# DAC_STM32_Board_v4_-_AD5391.net
KiCad netlist of a schematic drawn in EAGLE
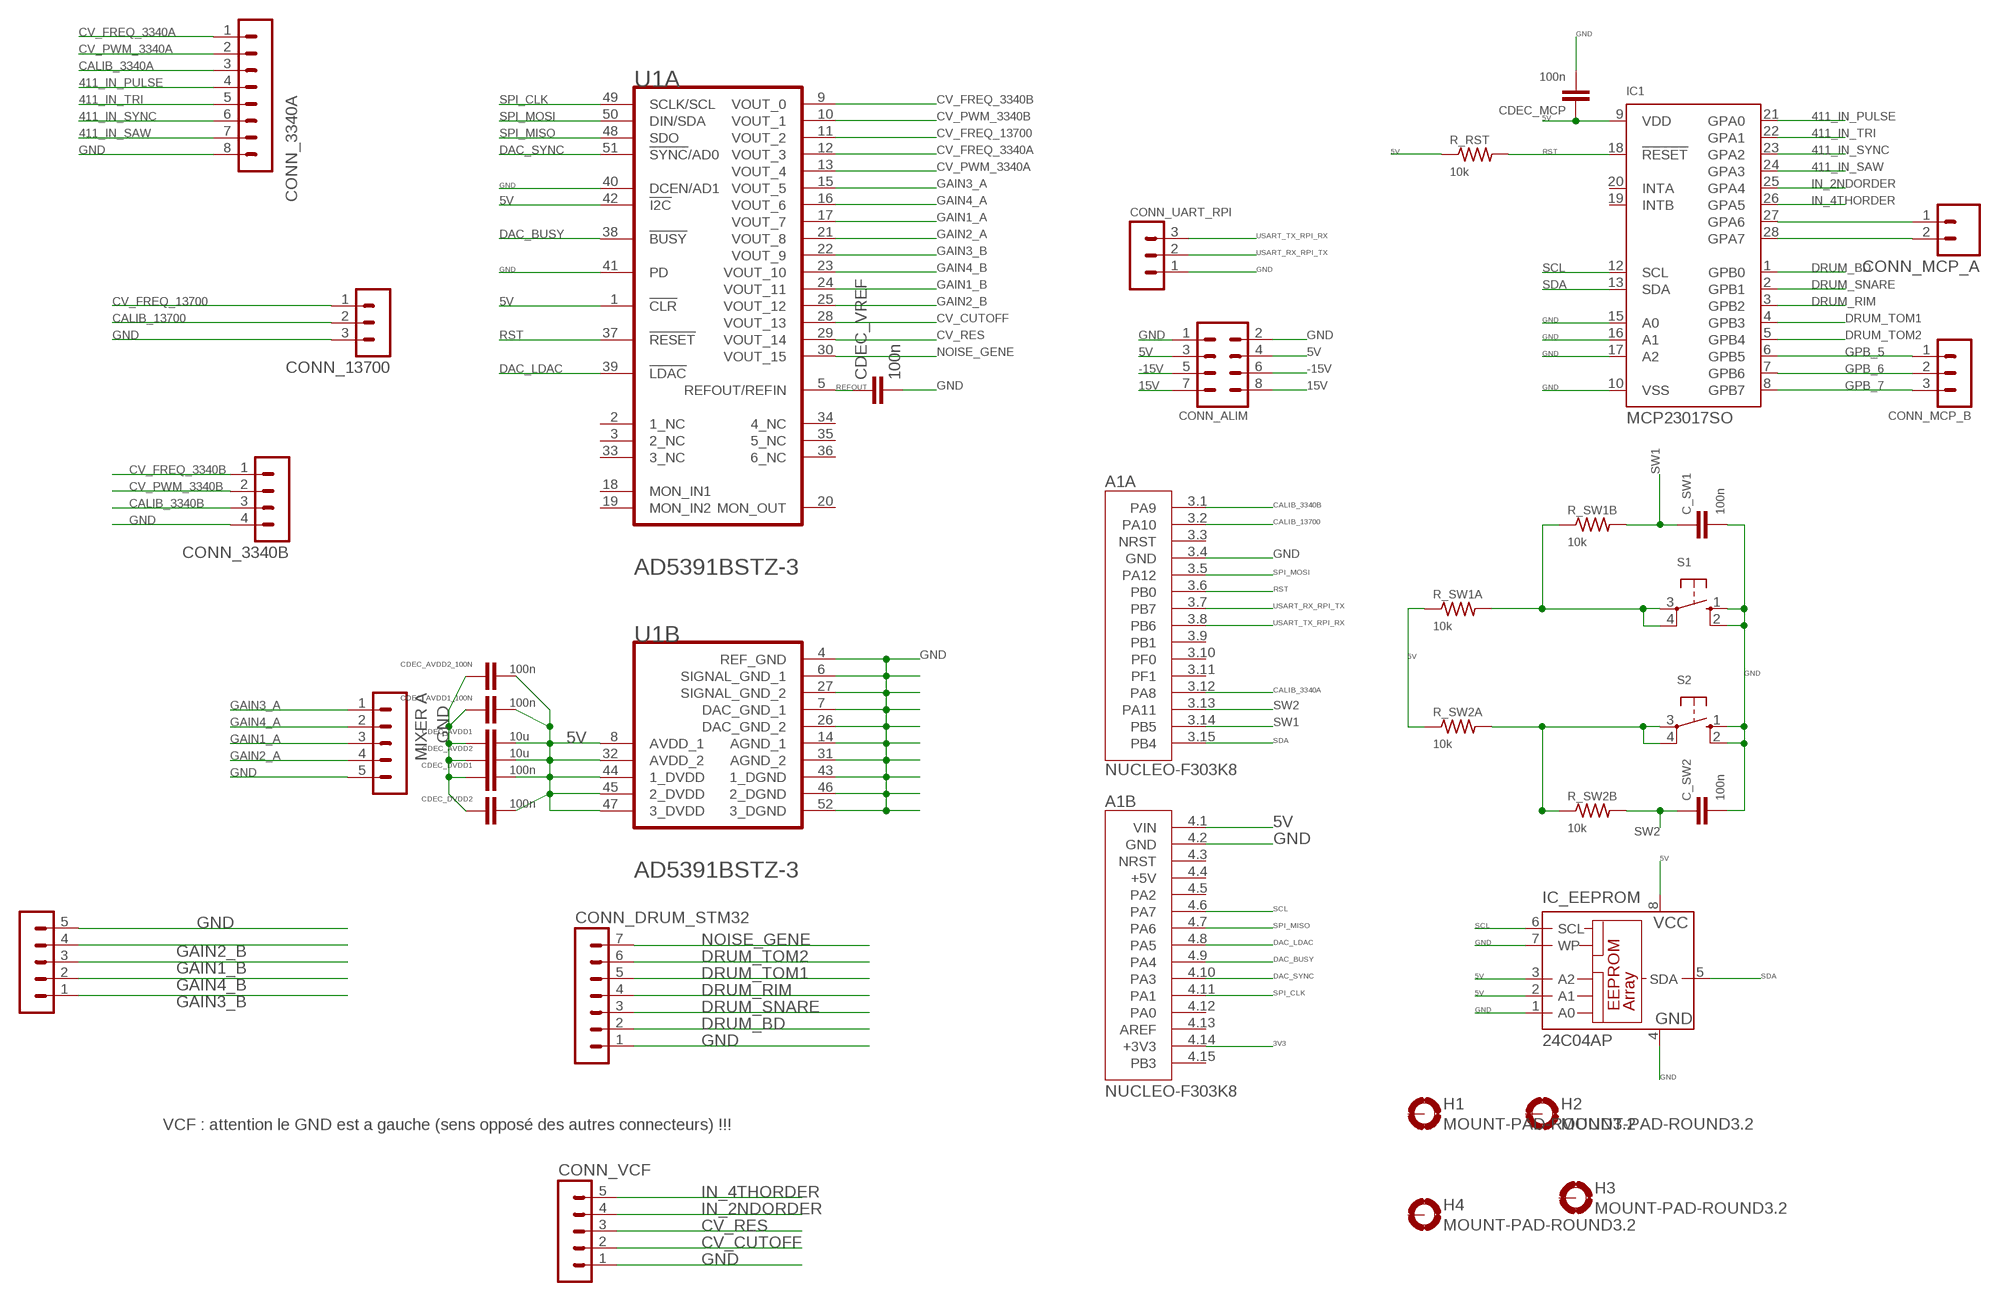
[diagram p0: schematic, sheet 1]

(export (version "E")
  (design (tool "Eeschema 10.0.6"))
  (components
    (comp (ref "A1")
      (value "NUCLEO-F303K8")
      (footprint "eagle-import:MODULE_NUCLEO-F303K8")
      (fields (field (name "DIGI-KEY_PART_NUMBER") "497-15981-ND") (field (name "MF") "STMicroelectronics"))
      (libsource (lib "eagle-import") (part "NUCLEO-F303K8"))
    )
    (comp (ref "CDEC_AVDD1")
      (value "10u")
      (footprint "eagle-import:C050-030X075")
      (libsource (lib "eagle-import") (part "C-EU050-030X075"))
    )
    (comp (ref "CDEC_AVDD1_100N")
      (value "100n")
      (footprint "eagle-import:C050-030X075")
      (libsource (lib "eagle-import") (part "C-EU050-030X075"))
    )
    (comp (ref "CDEC_AVDD2")
      (value "10u")
      (footprint "eagle-import:C050-030X075")
      (libsource (lib "eagle-import") (part "C-EU050-030X075"))
    )
    (comp (ref "CDEC_AVDD2_100N")
      (value "100n")
      (footprint "eagle-import:C050-030X075")
      (libsource (lib "eagle-import") (part "C-EU050-030X075"))
    )
    (comp (ref "CDEC_DVDD1")
      (value "100n")
      (footprint "eagle-import:C075-032X103")
      (libsource (lib "eagle-import") (part "C-EU075-032X103"))
    )
    (comp (ref "CDEC_DVDD2")
      (value "100n")
      (footprint "eagle-import:C050-030X075")
      (libsource (lib "eagle-import") (part "C-EU050-030X075"))
    )
    (comp (ref "CDEC_MCP")
      (value "100n")
      (footprint "eagle-import:C075-032X103")
      (libsource (lib "eagle-import") (part "C-EU075-032X103"))
    )
    (comp (ref "CDEC_VREF")
      (value "100n")
      (footprint "eagle-import:C050-030X075")
      (libsource (lib "eagle-import") (part "C-EU050-030X075"))
    )
    (comp (ref "CONN_3340A")
      (value "MA08-1")
      (footprint "eagle-import:MA08-1")
      (libsource (lib "eagle-import") (part "MA08-1"))
    )
    (comp (ref "CONN_3340B")
      (value "MA04-1")
      (footprint "eagle-import:MA04-1")
      (libsource (lib "eagle-import") (part "MA04-1"))
    )
    (comp (ref "CONN_13700")
      (value "MA03-1")
      (footprint "eagle-import:MA03-1")
      (libsource (lib "eagle-import") (part "MA03-1"))
    )
    (comp (ref "CONN_ALIM")
      (value "MA04-2")
      (footprint "eagle-import:MA04-2")
      (libsource (lib "eagle-import") (part "MA04-2"))
    )
    (comp (ref "CONN_DRUM_STM32")
      (value "MA07-1")
      (footprint "eagle-import:MA07-1")
      (libsource (lib "eagle-import") (part "MA07-1"))
    )
    (comp (ref "CONN_MCP_A")
      (value "M02")
      (footprint "eagle-import:02P")
      (libsource (lib "eagle-import") (part "M02"))
    )
    (comp (ref "CONN_MCP_B")
      (value "MA03-1")
      (footprint "eagle-import:MA03-1")
      (libsource (lib "eagle-import") (part "MA03-1"))
    )
    (comp (ref "CONN_MIX_A")
      (value "MA05-1")
      (footprint "eagle-import:MA05-1")
      (libsource (lib "eagle-import") (part "MA05-1"))
    )
    (comp (ref "CONN_MIX_B")
      (value "MA05-1")
      (footprint "eagle-import:MA05-1")
      (libsource (lib "eagle-import") (part "MA05-1"))
    )
    (comp (ref "CONN_UART_RPI")
      (value "MA03-1")
      (footprint "eagle-import:MA03-1")
      (libsource (lib "eagle-import") (part "MA03-1"))
    )
    (comp (ref "CONN_VCF")
      (value "MA05-1")
      (footprint "eagle-import:MA05-1")
      (libsource (lib "eagle-import") (part "MA05-1"))
    )
    (comp (ref "C_SW1")
      (value "100n")
      (footprint "eagle-import:C050-030X075")
      (libsource (lib "eagle-import") (part "C-EU050-030X075"))
    )
    (comp (ref "C_SW2")
      (value "100n")
      (footprint "eagle-import:C050-030X075")
      (libsource (lib "eagle-import") (part "C-EU050-030X075"))
    )
    (comp (ref "H1")
      (value "MOUNT-PAD-ROUND3.2")
      (footprint "eagle-import:3,2-PAD")
      (libsource (lib "eagle-import") (part "MOUNT-PAD-ROUND3.2"))
    )
    (comp (ref "H2")
      (value "MOUNT-PAD-ROUND3.2")
      (footprint "eagle-import:3,2-PAD")
      (libsource (lib "eagle-import") (part "MOUNT-PAD-ROUND3.2"))
    )
    (comp (ref "H3")
      (value "MOUNT-PAD-ROUND3.2")
      (footprint "eagle-import:3,2-PAD")
      (libsource (lib "eagle-import") (part "MOUNT-PAD-ROUND3.2"))
    )
    (comp (ref "H4")
      (value "MOUNT-PAD-ROUND3.2")
      (footprint "eagle-import:3,2-PAD")
      (libsource (lib "eagle-import") (part "MOUNT-PAD-ROUND3.2"))
    )
    (comp (ref "IC1")
      (value "MCP23017SO")
      (footprint "eagle-import:SO28W")
      (fields (field (name "MF") "MICROCHIP") (field (name "MPN") "MCP23017-E/SO"))
      (libsource (lib "eagle-import") (part "MCP23017SO"))
    )
    (comp (ref "IC_EEPROM")
      (value "24C04AP")
      (footprint "eagle-import:DIL8")
      (fields (field (name "MPN") "AT24C04B-PU"))
      (libsource (lib "eagle-import") (part "24CP04A"))
    )
    (comp (ref "R_RST")
      (value "10k")
      (footprint "eagle-import:0207_10")
      (libsource (lib "eagle-import") (part "R-US_0207/10"))
    )
    (comp (ref "R_SW1A")
      (value "10k")
      (footprint "eagle-import:0207_10")
      (libsource (lib "eagle-import") (part "R-US_0207/10"))
    )
    (comp (ref "R_SW1B")
      (value "10k")
      (footprint "eagle-import:0207_10")
      (libsource (lib "eagle-import") (part "R-US_0207/10"))
    )
    (comp (ref "R_SW2A")
      (value "10k")
      (footprint "eagle-import:0207_10")
      (libsource (lib "eagle-import") (part "R-US_0207/10"))
    )
    (comp (ref "R_SW2B")
      (value "10k")
      (footprint "eagle-import:0207_10")
      (libsource (lib "eagle-import") (part "R-US_0207/10"))
    )
    (comp (ref "S1")
      (value "10-XX")
      (footprint "eagle-import:B3F-10XX")
      (fields (field (name "MPN") "B3F-1000"))
      (libsource (lib "eagle-import") (part "10-XX"))
    )
    (comp (ref "S2")
      (value "10-XX")
      (footprint "eagle-import:B3F-10XX")
      (fields (field (name "MPN") "B3F-1000"))
      (libsource (lib "eagle-import") (part "10-XX"))
    )
    (comp (ref "U1")
      (value "ANALOG_DEVICES_AD5391BSTZ-3ANALOG_DEVICES_AD5391BSTZ-3_0_0")
      (footprint "eagle-import:ANALOG_DEVICES_AD5391BSTZ-3_0")
      (fields (field (name "MF") "Analog Devices") (field (name "MPN") "AD5391BSTZ-3"))
      (libsource (lib "eagle-import") (part "ANALOG_DEVICES_AD5391BSTZ-3ANALOG_DEVICES_AD5391BSTZ-3_0_0"))
    )
  )
  (nets
    (net (code "1") (name "/-15V") (class "Default")
      (node (ref "CONN_ALIM") (pin "5") (pinfunction "5_5") (pintype "passive"))
      (node (ref "CONN_ALIM") (pin "6") (pinfunction "6_6") (pintype "passive"))
    )
    (net (code "2") (name "/3V3") (class "Default")
      (node (ref "A1") (pin "4.14") (pinfunction "+3V3_4.14") (pintype "bidirectional"))
    )
    (net (code "3") (name "/5V") (class "Default")
      (node (ref "A1") (pin "4.1") (pinfunction "VIN_4.1") (pintype "bidirectional"))
      (node (ref "CDEC_AVDD1") (pin "2") (pinfunction "2_2") (pintype "passive"))
      (node (ref "CDEC_AVDD1_100N") (pin "2") (pinfunction "2_2") (pintype "passive"))
      (node (ref "CDEC_AVDD2") (pin "2") (pinfunction "2_2") (pintype "passive"))
      (node (ref "CDEC_AVDD2_100N") (pin "2") (pinfunction "2_2") (pintype "passive"))
      (node (ref "CDEC_DVDD1") (pin "2") (pinfunction "2_2") (pintype "passive"))
      (node (ref "CDEC_DVDD2") (pin "2") (pinfunction "2_2") (pintype "passive"))
      (node (ref "CDEC_MCP") (pin "1") (pinfunction "1_1") (pintype "passive"))
      (node (ref "CONN_ALIM") (pin "3") (pinfunction "3_3") (pintype "passive"))
      (node (ref "CONN_ALIM") (pin "4") (pinfunction "4_4") (pintype "passive"))
      (node (ref "IC1") (pin "9") (pinfunction "VDD_9") (pintype "power_in"))
      (node (ref "IC_EEPROM") (pin "2") (pinfunction "A1_2") (pintype "input"))
      (node (ref "IC_EEPROM") (pin "3") (pinfunction "A2_3") (pintype "input"))
      (node (ref "IC_EEPROM") (pin "8") (pinfunction "VCC_8") (pintype "power_in"))
      (node (ref "R_RST") (pin "1") (pinfunction "1_1") (pintype "passive"))
      (node (ref "R_SW1A") (pin "1") (pinfunction "1_1") (pintype "passive"))
      (node (ref "R_SW2A") (pin "1") (pinfunction "1_1") (pintype "passive"))
      (node (ref "U1") (pin "1") (pinfunction "~{CLR}_1") (pintype "input"))
      (node (ref "U1") (pin "32") (pinfunction "AVDD_2_32") (pintype "power_in"))
      (node (ref "U1") (pin "42") (pinfunction "~{I2C}_42") (pintype "input"))
      (node (ref "U1") (pin "44") (pinfunction "1_DVDD_44") (pintype "power_in"))
      (node (ref "U1") (pin "45") (pinfunction "2_DVDD_45") (pintype "power_in"))
      (node (ref "U1") (pin "47") (pinfunction "3_DVDD_47") (pintype "power_in"))
      (node (ref "U1") (pin "8") (pinfunction "AVDD_1_8") (pintype "power_in"))
    )
    (net (code "4") (name "/15V") (class "Default")
      (node (ref "CONN_ALIM") (pin "7") (pinfunction "7_7") (pintype "passive"))
      (node (ref "CONN_ALIM") (pin "8") (pinfunction "8_8") (pintype "passive"))
    )
    (net (code "5") (name "/411_IN_PULSE") (class "Default")
      (node (ref "CONN_3340A") (pin "4") (pinfunction "4_4") (pintype "passive"))
      (node (ref "IC1") (pin "21") (pinfunction "GPA0_21") (pintype "bidirectional"))
    )
    (net (code "6") (name "/411_IN_SAW") (class "Default")
      (node (ref "CONN_3340A") (pin "7") (pinfunction "7_7") (pintype "passive"))
      (node (ref "IC1") (pin "24") (pinfunction "GPA3_24") (pintype "bidirectional"))
    )
    (net (code "7") (name "/411_IN_SYNC") (class "Default")
      (node (ref "CONN_3340A") (pin "6") (pinfunction "6_6") (pintype "passive"))
      (node (ref "IC1") (pin "23") (pinfunction "GPA2_23") (pintype "bidirectional"))
    )
    (net (code "8") (name "/411_IN_TRI") (class "Default")
      (node (ref "CONN_3340A") (pin "5") (pinfunction "5_5") (pintype "passive"))
      (node (ref "IC1") (pin "22") (pinfunction "GPA1_22") (pintype "bidirectional"))
    )
    (net (code "9") (name "/CALIB_3340A") (class "Default")
      (node (ref "A1") (pin "3.12") (pinfunction "PA8_3.12") (pintype "bidirectional"))
      (node (ref "CONN_3340A") (pin "3") (pinfunction "3_3") (pintype "passive"))
    )
    (net (code "10") (name "/CALIB_3340B") (class "Default")
      (node (ref "A1") (pin "3.1") (pinfunction "PA9_3.1") (pintype "bidirectional"))
      (node (ref "CONN_3340B") (pin "3") (pinfunction "3_3") (pintype "passive"))
    )
    (net (code "11") (name "/CALIB_13700") (class "Default")
      (node (ref "A1") (pin "3.2") (pinfunction "PA10_3.2") (pintype "bidirectional"))
      (node (ref "CONN_13700") (pin "2") (pinfunction "2_2") (pintype "passive"))
    )
    (net (code "12") (name "/CV_CUTOFF") (class "Default")
      (node (ref "CONN_VCF") (pin "2") (pinfunction "2_2") (pintype "passive"))
      (node (ref "U1") (pin "28") (pinfunction "VOUT_13_28") (pintype "tri_state"))
    )
    (net (code "13") (name "/CV_FREQ_3340A") (class "Default")
      (node (ref "CONN_3340A") (pin "1") (pinfunction "1_1") (pintype "passive"))
      (node (ref "U1") (pin "12") (pinfunction "VOUT_3_12") (pintype "tri_state"))
    )
    (net (code "14") (name "/CV_FREQ_3340B") (class "Default")
      (node (ref "CONN_3340B") (pin "1") (pinfunction "1_1") (pintype "passive"))
      (node (ref "U1") (pin "9") (pinfunction "VOUT_0_9") (pintype "tri_state"))
    )
    (net (code "15") (name "/CV_FREQ_13700") (class "Default")
      (node (ref "CONN_13700") (pin "1") (pinfunction "1_1") (pintype "passive"))
      (node (ref "U1") (pin "11") (pinfunction "VOUT_2_11") (pintype "tri_state"))
    )
    (net (code "16") (name "/CV_PWM_3340A") (class "Default")
      (node (ref "CONN_3340A") (pin "2") (pinfunction "2_2") (pintype "passive"))
      (node (ref "U1") (pin "13") (pinfunction "VOUT_4_13") (pintype "tri_state"))
    )
    (net (code "17") (name "/CV_PWM_3340B") (class "Default")
      (node (ref "CONN_3340B") (pin "2") (pinfunction "2_2") (pintype "passive"))
      (node (ref "U1") (pin "10") (pinfunction "VOUT_1_10") (pintype "tri_state"))
    )
    (net (code "18") (name "/CV_RES") (class "Default")
      (node (ref "CONN_VCF") (pin "3") (pinfunction "3_3") (pintype "passive"))
      (node (ref "U1") (pin "29") (pinfunction "VOUT_14_29") (pintype "tri_state"))
    )
    (net (code "19") (name "/DAC_BUSY") (class "Default")
      (node (ref "A1") (pin "4.9") (pinfunction "PA4_4.9") (pintype "bidirectional"))
      (node (ref "U1") (pin "38") (pinfunction "~{BUSY}_38") (pintype "output"))
    )
    (net (code "20") (name "/DAC_LDAC") (class "Default")
      (node (ref "A1") (pin "4.8") (pinfunction "PA5_4.8") (pintype "bidirectional"))
      (node (ref "U1") (pin "39") (pinfunction "~{LDAC}_39") (pintype "input"))
    )
    (net (code "21") (name "/DAC_SYNC") (class "Default")
      (node (ref "A1") (pin "4.10") (pinfunction "PA3_4.10") (pintype "bidirectional"))
      (node (ref "U1") (pin "51") (pinfunction "~{SYNC}/AD0_51") (pintype "input"))
    )
    (net (code "22") (name "/DRUM_BD") (class "Default")
      (node (ref "CONN_DRUM_STM32") (pin "2") (pinfunction "2_2") (pintype "passive"))
      (node (ref "IC1") (pin "1") (pinfunction "GPB0_1") (pintype "bidirectional"))
    )
    (net (code "23") (name "/DRUM_RIM") (class "Default")
      (node (ref "CONN_DRUM_STM32") (pin "4") (pinfunction "4_4") (pintype "passive"))
      (node (ref "IC1") (pin "3") (pinfunction "GPB2_3") (pintype "bidirectional"))
    )
    (net (code "24") (name "/DRUM_SNARE") (class "Default")
      (node (ref "CONN_DRUM_STM32") (pin "3") (pinfunction "3_3") (pintype "passive"))
      (node (ref "IC1") (pin "2") (pinfunction "GPB1_2") (pintype "bidirectional"))
    )
    (net (code "25") (name "/DRUM_TOM1") (class "Default")
      (node (ref "CONN_DRUM_STM32") (pin "5") (pinfunction "5_5") (pintype "passive"))
      (node (ref "IC1") (pin "4") (pinfunction "GPB3_4") (pintype "bidirectional"))
    )
    (net (code "26") (name "/DRUM_TOM2") (class "Default")
      (node (ref "CONN_DRUM_STM32") (pin "6") (pinfunction "6_6") (pintype "passive"))
      (node (ref "IC1") (pin "5") (pinfunction "GPB4_5") (pintype "bidirectional"))
    )
    (net (code "27") (name "/GAIN1_A") (class "Default")
      (node (ref "CONN_MIX_A") (pin "3") (pinfunction "3_3") (pintype "passive"))
      (node (ref "U1") (pin "17") (pinfunction "VOUT_7_17") (pintype "tri_state"))
    )
    (net (code "28") (name "/GAIN1_B") (class "Default")
      (node (ref "CONN_MIX_B") (pin "3") (pinfunction "3_3") (pintype "passive"))
      (node (ref "U1") (pin "24") (pinfunction "VOUT_11_24") (pintype "tri_state"))
    )
    (net (code "29") (name "/GAIN2_A") (class "Default")
      (node (ref "CONN_MIX_A") (pin "4") (pinfunction "4_4") (pintype "passive"))
      (node (ref "U1") (pin "21") (pinfunction "VOUT_8_21") (pintype "tri_state"))
    )
    (net (code "30") (name "/GAIN2_B") (class "Default")
      (node (ref "CONN_MIX_B") (pin "4") (pinfunction "4_4") (pintype "passive"))
      (node (ref "U1") (pin "25") (pinfunction "VOUT_12_25") (pintype "tri_state"))
    )
    (net (code "31") (name "/GAIN3_A") (class "Default")
      (node (ref "CONN_MIX_A") (pin "1") (pinfunction "1_1") (pintype "passive"))
      (node (ref "U1") (pin "15") (pinfunction "VOUT_5_15") (pintype "tri_state"))
    )
    (net (code "32") (name "/GAIN3_B") (class "Default")
      (node (ref "CONN_MIX_B") (pin "1") (pinfunction "1_1") (pintype "passive"))
      (node (ref "U1") (pin "22") (pinfunction "VOUT_9_22") (pintype "tri_state"))
    )
    (net (code "33") (name "/GAIN4_A") (class "Default")
      (node (ref "CONN_MIX_A") (pin "2") (pinfunction "2_2") (pintype "passive"))
      (node (ref "U1") (pin "16") (pinfunction "VOUT_6_16") (pintype "tri_state"))
    )
    (net (code "34") (name "/GAIN4_B") (class "Default")
      (node (ref "CONN_MIX_B") (pin "2") (pinfunction "2_2") (pintype "passive"))
      (node (ref "U1") (pin "23") (pinfunction "VOUT_10_23") (pintype "tri_state"))
    )
    (net (code "35") (name "/GND") (class "Default")
      (node (ref "A1") (pin "3.4") (pinfunction "GND_3.4") (pintype "bidirectional"))
      (node (ref "A1") (pin "4.2") (pinfunction "GND_4.2") (pintype "bidirectional"))
      (node (ref "CDEC_AVDD1") (pin "1") (pinfunction "1_1") (pintype "passive"))
      (node (ref "CDEC_AVDD1_100N") (pin "1") (pinfunction "1_1") (pintype "passive"))
      (node (ref "CDEC_AVDD2") (pin "1") (pinfunction "1_1") (pintype "passive"))
      (node (ref "CDEC_AVDD2_100N") (pin "1") (pinfunction "1_1") (pintype "passive"))
      (node (ref "CDEC_DVDD1") (pin "1") (pinfunction "1_1") (pintype "passive"))
      (node (ref "CDEC_DVDD2") (pin "1") (pinfunction "1_1") (pintype "passive"))
      (node (ref "CDEC_MCP") (pin "2") (pinfunction "2_2") (pintype "passive"))
      (node (ref "CDEC_VREF") (pin "2") (pinfunction "2_2") (pintype "passive"))
      (node (ref "CONN_13700") (pin "3") (pinfunction "3_3") (pintype "passive"))
      (node (ref "CONN_3340A") (pin "8") (pinfunction "8_8") (pintype "passive"))
      (node (ref "CONN_3340B") (pin "4") (pinfunction "4_4") (pintype "passive"))
      (node (ref "CONN_ALIM") (pin "1") (pinfunction "1_1") (pintype "passive"))
      (node (ref "CONN_ALIM") (pin "2") (pinfunction "2_2") (pintype "passive"))
      (node (ref "CONN_DRUM_STM32") (pin "1") (pinfunction "1_1") (pintype "passive"))
      (node (ref "CONN_MIX_A") (pin "5") (pinfunction "5_5") (pintype "passive"))
      (node (ref "CONN_MIX_B") (pin "5") (pinfunction "5_5") (pintype "passive"))
      (node (ref "CONN_UART_RPI") (pin "1") (pinfunction "1_1") (pintype "passive"))
      (node (ref "CONN_VCF") (pin "1") (pinfunction "1_1") (pintype "passive"))
      (node (ref "C_SW1") (pin "2") (pinfunction "2_2") (pintype "passive"))
      (node (ref "C_SW2") (pin "2") (pinfunction "2_2") (pintype "passive"))
      (node (ref "IC1") (pin "10") (pinfunction "VSS_10") (pintype "power_in"))
      (node (ref "IC1") (pin "15") (pinfunction "A0_15") (pintype "input"))
      (node (ref "IC1") (pin "16") (pinfunction "A1_16") (pintype "input"))
      (node (ref "IC1") (pin "17") (pinfunction "A2_17") (pintype "input"))
      (node (ref "IC_EEPROM") (pin "1") (pinfunction "A0_1") (pintype "input"))
      (node (ref "IC_EEPROM") (pin "4") (pinfunction "GND_4") (pintype "power_in"))
      (node (ref "IC_EEPROM") (pin "7") (pinfunction "WP_7") (pintype "input"))
      (node (ref "S1") (pin "1") (pinfunction "S_1") (pintype "passive"))
      (node (ref "S1") (pin "2") (pinfunction "S1_2") (pintype "passive"))
      (node (ref "S2") (pin "1") (pinfunction "S_1") (pintype "passive"))
      (node (ref "S2") (pin "2") (pinfunction "S1_2") (pintype "passive"))
      (node (ref "U1") (pin "14") (pinfunction "AGND_1_14") (pintype "power_in"))
      (node (ref "U1") (pin "26") (pinfunction "DAC_GND_2_26") (pintype "power_in"))
      (node (ref "U1") (pin "27") (pinfunction "SIGNAL_GND_2_27") (pintype "power_in"))
      (node (ref "U1") (pin "31") (pinfunction "AGND_2_31") (pintype "power_in"))
      (node (ref "U1") (pin "4") (pinfunction "REF_GND_4") (pintype "power_in"))
      (node (ref "U1") (pin "40") (pinfunction "DCEN/AD1_40") (pintype "input"))
      (node (ref "U1") (pin "41") (pinfunction "PD_41") (pintype "input"))
      (node (ref "U1") (pin "43") (pinfunction "1_DGND_43") (pintype "power_in"))
      (node (ref "U1") (pin "46") (pinfunction "2_DGND_46") (pintype "power_in"))
      (node (ref "U1") (pin "52") (pinfunction "3_DGND_52") (pintype "power_in"))
      (node (ref "U1") (pin "6") (pinfunction "SIGNAL_GND_1_6") (pintype "power_in"))
      (node (ref "U1") (pin "7") (pinfunction "DAC_GND_1_7") (pintype "power_in"))
    )
    (net (code "36") (name "/GPB_5") (class "Default")
      (node (ref "CONN_MCP_B") (pin "1") (pinfunction "1_1") (pintype "passive"))
      (node (ref "IC1") (pin "6") (pinfunction "GPB5_6") (pintype "bidirectional"))
    )
    (net (code "37") (name "/GPB_6") (class "Default")
      (node (ref "CONN_MCP_B") (pin "2") (pinfunction "2_2") (pintype "passive"))
      (node (ref "IC1") (pin "7") (pinfunction "GPB6_7") (pintype "bidirectional"))
    )
    (net (code "38") (name "/GPB_7") (class "Default")
      (node (ref "CONN_MCP_B") (pin "3") (pinfunction "3_3") (pintype "passive"))
      (node (ref "IC1") (pin "8") (pinfunction "GPB7_8") (pintype "bidirectional"))
    )
    (net (code "39") (name "/IN_2NDORDER") (class "Default")
      (node (ref "CONN_VCF") (pin "4") (pinfunction "4_4") (pintype "passive"))
      (node (ref "IC1") (pin "25") (pinfunction "GPA4_25") (pintype "bidirectional"))
    )
    (net (code "40") (name "/IN_4THORDER") (class "Default")
      (node (ref "CONN_VCF") (pin "5") (pinfunction "5_5") (pintype "passive"))
      (node (ref "IC1") (pin "26") (pinfunction "GPA5_26") (pintype "bidirectional"))
    )
    (net (code "41") (name "/NOISE_GENE") (class "Default")
      (node (ref "CONN_DRUM_STM32") (pin "7") (pinfunction "7_7") (pintype "passive"))
      (node (ref "U1") (pin "30") (pinfunction "VOUT_15_30") (pintype "tri_state"))
    )
    (net (code "42") (name "/REFOUT") (class "Default")
      (node (ref "CDEC_VREF") (pin "1") (pinfunction "1_1") (pintype "passive"))
      (node (ref "U1") (pin "5") (pinfunction "REFOUT/REFIN_5") (pintype "bidirectional"))
    )
    (net (code "43") (name "/RST") (class "Default")
      (node (ref "A1") (pin "3.6") (pinfunction "PB0_3.6") (pintype "bidirectional"))
      (node (ref "IC1") (pin "18") (pinfunction "~{RESET}_18") (pintype "input"))
      (node (ref "R_RST") (pin "2") (pinfunction "2_2") (pintype "passive"))
      (node (ref "U1") (pin "37") (pinfunction "~{RESET}_37") (pintype "input"))
    )
    (net (code "44") (name "/SCL") (class "Default")
      (node (ref "A1") (pin "4.6") (pinfunction "PA7_4.6") (pintype "bidirectional"))
      (node (ref "IC1") (pin "12") (pinfunction "SCL_12") (pintype "input"))
      (node (ref "IC_EEPROM") (pin "6") (pinfunction "SCL_6") (pintype "input"))
    )
    (net (code "45") (name "/SDA") (class "Default")
      (node (ref "A1") (pin "3.15") (pinfunction "PB4_3.15") (pintype "bidirectional"))
      (node (ref "IC1") (pin "13") (pinfunction "SDA_13") (pintype "bidirectional"))
      (node (ref "IC_EEPROM") (pin "5") (pinfunction "SDA_5") (pintype "bidirectional"))
    )
    (net (code "46") (name "/SPI_CLK") (class "Default")
      (node (ref "A1") (pin "4.11") (pinfunction "PA1_4.11") (pintype "bidirectional"))
      (node (ref "U1") (pin "49") (pinfunction "SCLK/SCL_49") (pintype "input"))
    )
    (net (code "47") (name "/SPI_MISO") (class "Default")
      (node (ref "A1") (pin "4.7") (pinfunction "PA6_4.7") (pintype "bidirectional"))
      (node (ref "U1") (pin "48") (pinfunction "SDO_48") (pintype "tri_state"))
    )
    (net (code "48") (name "/SPI_MOSI") (class "Default")
      (node (ref "A1") (pin "3.5") (pinfunction "PA12_3.5") (pintype "bidirectional"))
      (node (ref "U1") (pin "50") (pinfunction "DIN/SDA_50") (pintype "bidirectional"))
    )
    (net (code "49") (name "/SW1") (class "Default")
      (node (ref "A1") (pin "3.14") (pinfunction "PB5_3.14") (pintype "bidirectional"))
      (node (ref "C_SW1") (pin "1") (pinfunction "1_1") (pintype "passive"))
      (node (ref "R_SW1B") (pin "2") (pinfunction "2_2") (pintype "passive"))
    )
    (net (code "50") (name "/SW2") (class "Default")
      (node (ref "A1") (pin "3.13") (pinfunction "PA11_3.13") (pintype "bidirectional"))
      (node (ref "C_SW2") (pin "1") (pinfunction "1_1") (pintype "passive"))
      (node (ref "R_SW2B") (pin "2") (pinfunction "2_2") (pintype "passive"))
    )
    (net (code "51") (name "/USART_RX_RPI_TX") (class "Default")
      (node (ref "A1") (pin "3.7") (pinfunction "PB7_3.7") (pintype "bidirectional"))
      (node (ref "CONN_UART_RPI") (pin "2") (pinfunction "2_2") (pintype "passive"))
    )
    (net (code "52") (name "/USART_TX_RPI_RX") (class "Default")
      (node (ref "A1") (pin "3.8") (pinfunction "PB6_3.8") (pintype "bidirectional"))
      (node (ref "CONN_UART_RPI") (pin "3") (pinfunction "3_3") (pintype "passive"))
    )
    (net (code "53") (name "Net-(IC1-GPA6)") (class "Default")
      (node (ref "CONN_MCP_A") (pin "1") (pinfunction "1_1") (pintype "passive"))
      (node (ref "IC1") (pin "27") (pinfunction "GPA6_27") (pintype "bidirectional"))
    )
    (net (code "54") (name "Net-(IC1-GPA7)") (class "Default")
      (node (ref "CONN_MCP_A") (pin "2") (pinfunction "2_2") (pintype "passive"))
      (node (ref "IC1") (pin "28") (pinfunction "GPA7_28") (pintype "bidirectional"))
    )
    (net (code "55") (name "Net-(S1-P)") (class "Default")
      (node (ref "R_SW1A") (pin "2") (pinfunction "2_2") (pintype "passive"))
      (node (ref "R_SW1B") (pin "1") (pinfunction "1_1") (pintype "passive"))
      (node (ref "S1") (pin "3") (pinfunction "P_3") (pintype "passive"))
      (node (ref "S1") (pin "4") (pinfunction "P1_4") (pintype "passive"))
    )
    (net (code "56") (name "Net-(S2-P)") (class "Default")
      (node (ref "R_SW2A") (pin "2") (pinfunction "2_2") (pintype "passive"))
      (node (ref "R_SW2B") (pin "1") (pinfunction "1_1") (pintype "passive"))
      (node (ref "S2") (pin "3") (pinfunction "P_3") (pintype "passive"))
      (node (ref "S2") (pin "4") (pinfunction "P1_4") (pintype "passive"))
    )
    (net (code "57") (name "unconnected-(A1A-NRST-Pad3.3)") (class "Default")
      (node (ref "A1") (pin "3.3") (pinfunction "NRST_3.3") (pintype "bidirectional"))
    )
    (net (code "58") (name "unconnected-(A1A-PB1-Pad3.9)") (class "Default")
      (node (ref "A1") (pin "3.9") (pinfunction "PB1_3.9") (pintype "bidirectional"))
    )
    (net (code "59") (name "unconnected-(A1A-PF0-Pad3.10)") (class "Default")
      (node (ref "A1") (pin "3.10") (pinfunction "PF0_3.10") (pintype "bidirectional"))
    )
    (net (code "60") (name "unconnected-(A1A-PF1-Pad3.11)") (class "Default")
      (node (ref "A1") (pin "3.11") (pinfunction "PF1_3.11") (pintype "bidirectional"))
    )
    (net (code "61") (name "unconnected-(A1B-+5V-Pad4.4)") (class "Default")
      (node (ref "A1") (pin "4.4") (pinfunction "+5V_4.4") (pintype "bidirectional"))
    )
    (net (code "62") (name "unconnected-(A1B-AREF-Pad4.13)") (class "Default")
      (node (ref "A1") (pin "4.13") (pinfunction "AREF_4.13") (pintype "bidirectional"))
    )
    (net (code "63") (name "unconnected-(A1B-NRST-Pad4.3)") (class "Default")
      (node (ref "A1") (pin "4.3") (pinfunction "NRST_4.3") (pintype "bidirectional"))
    )
    (net (code "64") (name "unconnected-(A1B-PA0-Pad4.12)") (class "Default")
      (node (ref "A1") (pin "4.12") (pinfunction "PA0_4.12") (pintype "bidirectional"))
    )
    (net (code "65") (name "unconnected-(A1B-PA2-Pad4.5)") (class "Default")
      (node (ref "A1") (pin "4.5") (pinfunction "PA2_4.5") (pintype "bidirectional"))
    )
    (net (code "66") (name "unconnected-(A1B-PB3-Pad4.15)") (class "Default")
      (node (ref "A1") (pin "4.15") (pinfunction "PB3_4.15") (pintype "bidirectional"))
    )
    (net (code "67") (name "unconnected-(H1-MOUNT-PadB3,2)") (class "Default")
      (node (ref "H1") (pin "B3,2") (pinfunction "MOUNT_B3,2") (pintype "passive"))
    )
    (net (code "68") (name "unconnected-(H2-MOUNT-PadB3,2)") (class "Default")
      (node (ref "H2") (pin "B3,2") (pinfunction "MOUNT_B3,2") (pintype "passive"))
    )
    (net (code "69") (name "unconnected-(H3-MOUNT-PadB3,2)") (class "Default")
      (node (ref "H3") (pin "B3,2") (pinfunction "MOUNT_B3,2") (pintype "passive"))
    )
    (net (code "70") (name "unconnected-(H4-MOUNT-PadB3,2)") (class "Default")
      (node (ref "H4") (pin "B3,2") (pinfunction "MOUNT_B3,2") (pintype "passive"))
    )
    (net (code "71") (name "unconnected-(IC1-INTA-Pad20)") (class "Default")
      (node (ref "IC1") (pin "20") (pinfunction "INTA_20") (pintype "output"))
    )
    (net (code "72") (name "unconnected-(IC1-INTB-Pad19)") (class "Default")
      (node (ref "IC1") (pin "19") (pinfunction "INTB_19") (pintype "output"))
    )
    (net (code "73") (name "unconnected-(U1A-1_NC-Pad2)") (class "Default")
      (node (ref "U1") (pin "2") (pinfunction "1_NC_2") (pintype "passive"))
    )
    (net (code "74") (name "unconnected-(U1A-2_NC-Pad3)") (class "Default")
      (node (ref "U1") (pin "3") (pinfunction "2_NC_3") (pintype "passive"))
    )
    (net (code "75") (name "unconnected-(U1A-3_NC-Pad33)") (class "Default")
      (node (ref "U1") (pin "33") (pinfunction "3_NC_33") (pintype "passive"))
    )
    (net (code "76") (name "unconnected-(U1A-4_NC-Pad34)") (class "Default")
      (node (ref "U1") (pin "34") (pinfunction "4_NC_34") (pintype "passive"))
    )
    (net (code "77") (name "unconnected-(U1A-5_NC-Pad35)") (class "Default")
      (node (ref "U1") (pin "35") (pinfunction "5_NC_35") (pintype "passive"))
    )
    (net (code "78") (name "unconnected-(U1A-6_NC-Pad36)") (class "Default")
      (node (ref "U1") (pin "36") (pinfunction "6_NC_36") (pintype "passive"))
    )
    (net (code "79") (name "unconnected-(U1A-MON_IN1-Pad18)") (class "Default")
      (node (ref "U1") (pin "18") (pinfunction "MON_IN1_18") (pintype "input"))
    )
    (net (code "80") (name "unconnected-(U1A-MON_IN2-Pad19)") (class "Default")
      (node (ref "U1") (pin "19") (pinfunction "MON_IN2_19") (pintype "input"))
    )
    (net (code "81") (name "unconnected-(U1A-MON_OUT-Pad20)") (class "Default")
      (node (ref "U1") (pin "20") (pinfunction "MON_OUT_20") (pintype "tri_state"))
    )
  )
)
